# Instrument.net
KiCad netlist of a schematic drawn in Altium Designer
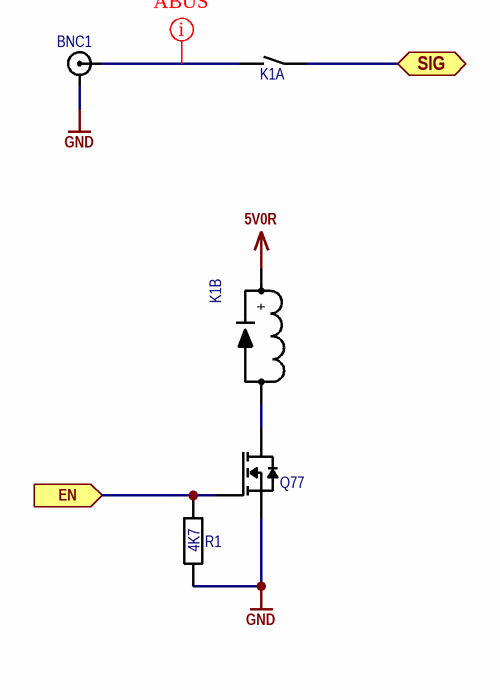
[diagram p0: Instrument.SchDoc]

(export (version "E")
  (design (tool "Eeschema 10.0.6"))
  (components
    (comp (ref "BNC1")
      (value "X")
      (footprint "BNC")
      (description "BNC Connector")
      (fields
        (field (name "02. DISTRIBUTOR PART NUMBER") "ACX1985-ND")
        (field (name "07. MANUFACTURER  PART NUMBER") "112778")
        (field (name "13. CREATED DATE/NAME") "AUG 2018 / Hören")
      )
      (libsource (lib "Connectors") (part "BNC"))
    )
    (comp (ref "K1")
      (value "K")
      (footprint "118-1A")
      (description "5V Signal Relais, Normal Open")
      (fields
        (field (name "02. DISTRIBUTOR PART NUMBER") "118-1-A-5/2D")
        (field (name "13. CREATED DATE/NAME") "20.12.17 S. Kaiser")
      )
      (libsource (lib "chickenfood") (part "118-1-A-5/2D"))
    )
    (comp (ref "Q77")
      (value "Q")
      (footprint "SOT23-3")
      (description "MOSFET N-CH 25V 680MA SOT-23")
      (fields
        (field (name "02. DISTRIBUTOR PART NUMBER") "FDV303NDKR-ND")
        (field (name "07. MANUFACTURER  PART NUMBER") "FDV303N")
        (field (name "13. CREATED DATE/NAME") "AUG 2018 / Hören")
      )
      (libsource (lib "SCT8-Board1") (part "FDV303N"))
    )
    (comp (ref "R1")
      (value "4K7")
      (footprint "R0603 Reflow")
      (description "RES SMD 4.7K OHM 1% 1/10W 0603")
      (fields
        (field (name "TOLERANCE") "±1%")
        (field (name "02. DISTRIBUTOR PART NUMBER") "311-4.70KHRCT-ND")
        (field (name "13. CREATED DATE/NAME") "AUG2018/Hören")
      )
      (libsource (lib "chickenfood") (part "R"))
    )
  )
  (nets
    (net (code "1") (name "/EN") (class "Default")
      (node (ref "Q77") (pin "1") (pinfunction "G_1") (pintype "passive"))
      (node (ref "R1") (pin "2") (pinfunction "2_2") (pintype "passive"))
    )
    (net (code "2") (name "/SIG") (class "Default")
      (node (ref "K1") (pin "4") (pinfunction "CB_4") (pintype "passive"))
    )
    (net (code "3") (name "5V0R") (class "Default")
      (node (ref "K1") (pin "1") (pinfunction "+_1") (pintype "passive"))
    )
    (net (code "4") (name "GND") (class "Default")
      (node (ref "BNC1") (pin "0") (pinfunction "0_0") (pintype "passive"))
      (node (ref "Q77") (pin "2") (pinfunction "S_2") (pintype "passive"))
      (node (ref "R1") (pin "1") (pinfunction "1_1") (pintype "passive"))
    )
    (net (code "5") (name "Net-(K1A-CA)") (class "Default")
      (node (ref "BNC1") (pin "1") (pinfunction "1_1") (pintype "passive"))
      (node (ref "K1") (pin "3") (pinfunction "CA_3") (pintype "passive"))
    )
    (net (code "6") (name "Net-(K1B--)") (class "Default")
      (node (ref "K1") (pin "2") (pinfunction "-_2") (pintype "passive"))
      (node (ref "Q77") (pin "3") (pinfunction "D_3") (pintype "passive"))
    )
  )
)
